# LDAQ-MOD-ADC8.net
KiCad netlist of a schematic drawn in EAGLE
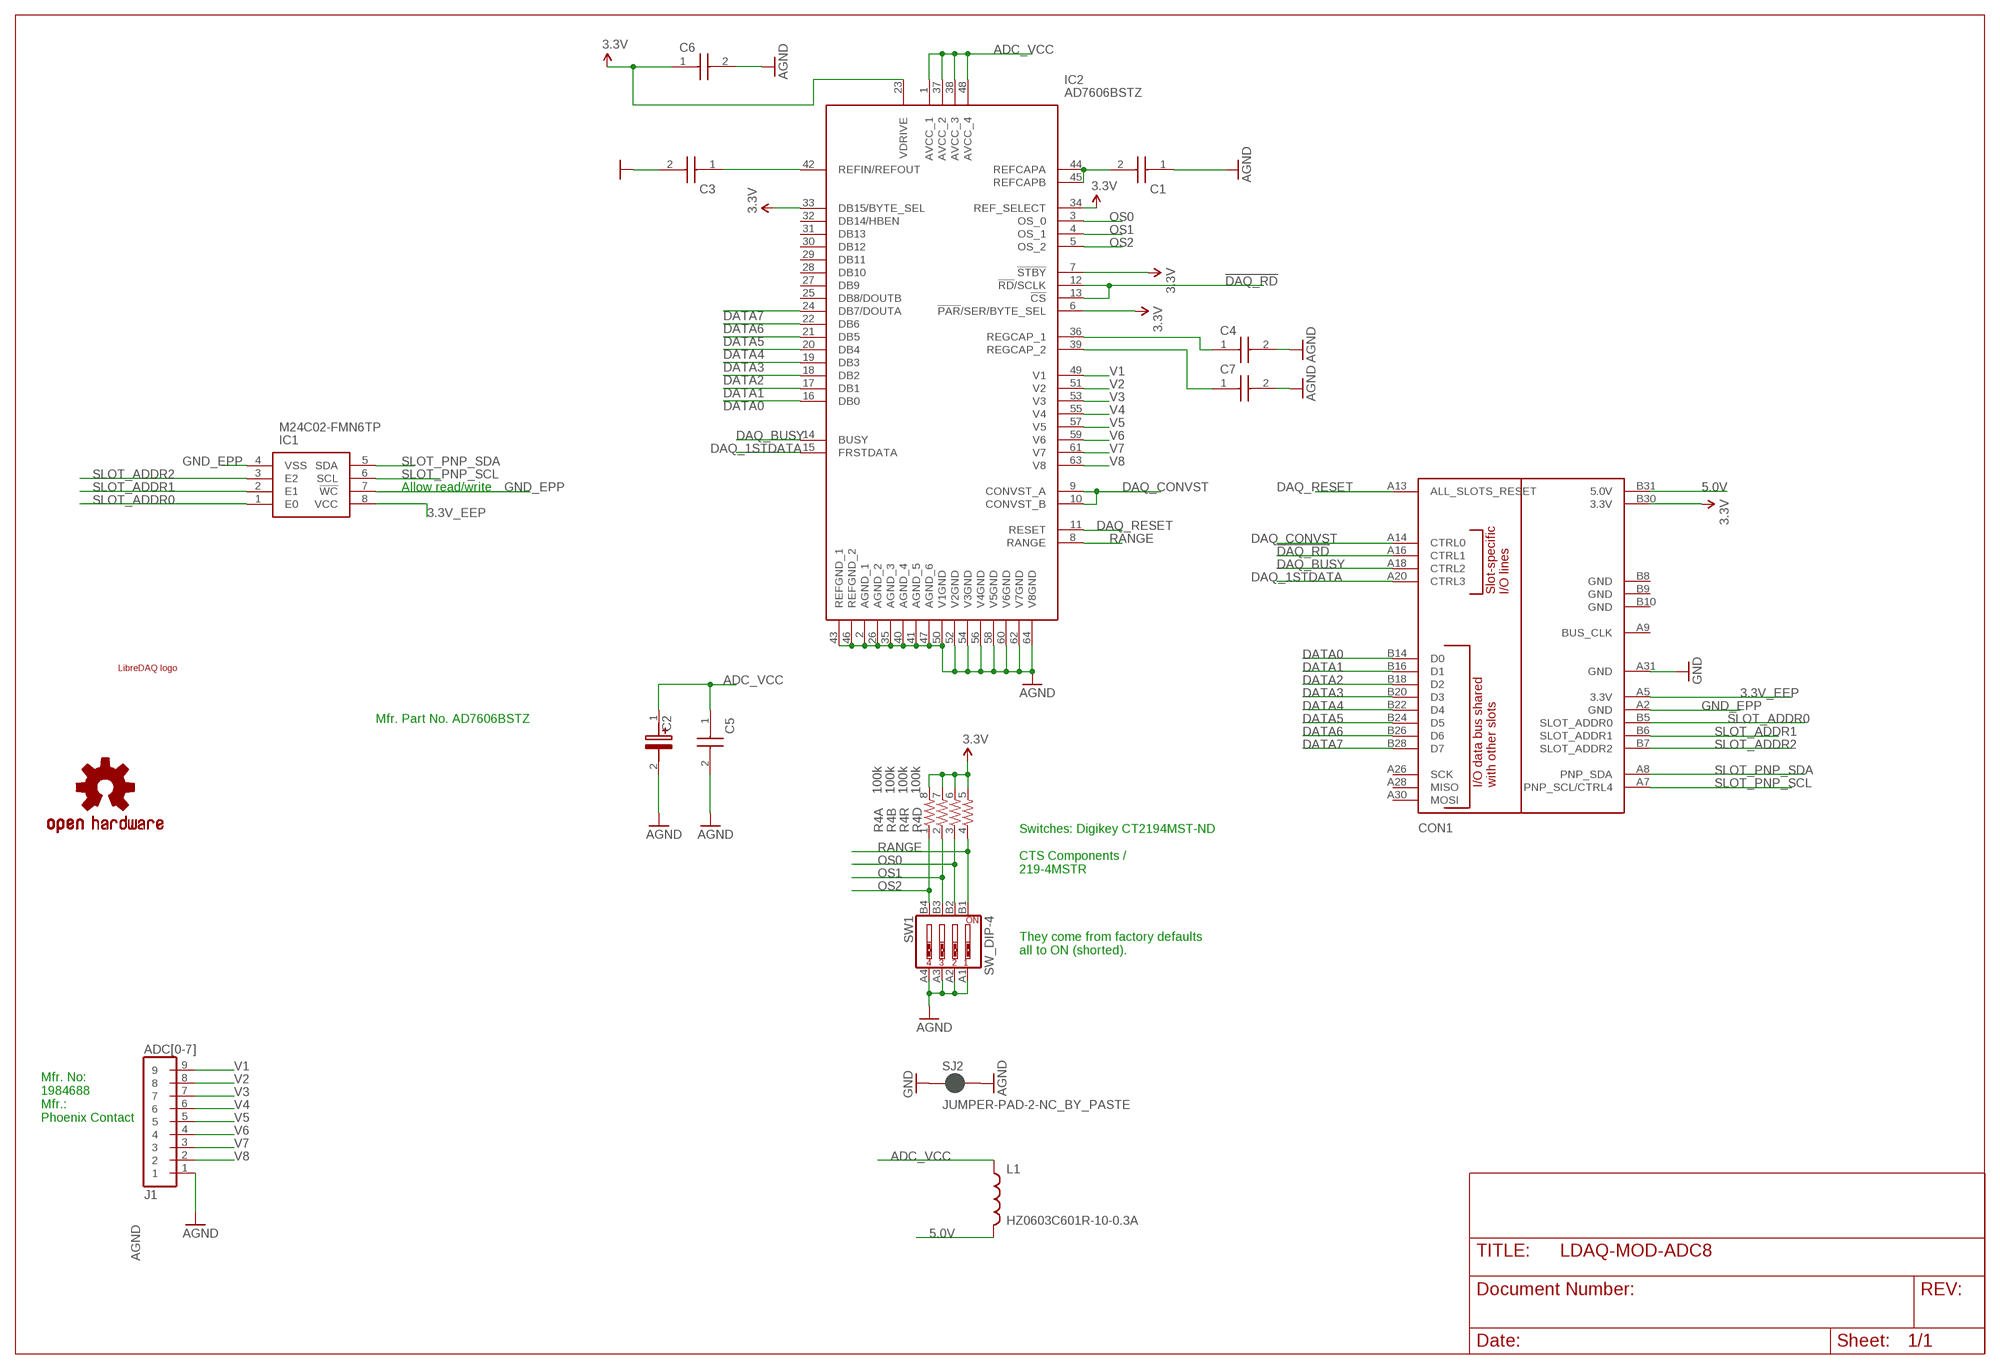
[diagram p0: schematic, sheet 1]

(export (version "E")
  (design (tool "Eeschema 10.0.6"))
  (components
    (comp (ref "C1")
      (value "10uF")
      (footprint "eagle-import:CAPC1005X55N")
      (fields
        (field (name "MANUFACTURER_PART_NUMBER") "LMK105BJ225KV-F")
        (field (name "MOUSER_PART_NUMBER") "963-LMK105BJ225KV-F")
      )
      (libsource (lib "eagle-import") (part "LMK105BJ225KV-F"))
    )
    (comp (ref "C2")
      (value "10uF")
      (footprint "eagle-import:CAPPM3528X210N")
      (fields
        (field (name "MANUFACTURER_PART_NUMBER") "TAJB226M010RNJ")
        (field (name "MOUSER_PART_NUMBER") "581-TAJB226M010R")
      )
      (libsource (lib "eagle-import") (part "TAJB226M010RNJ"))
    )
    (comp (ref "C3")
      (value "10uF")
      (footprint "eagle-import:CAPC1005X55N")
      (fields
        (field (name "MANUFACTURER_PART_NUMBER") "LMK105BJ225KV-F")
        (field (name "MOUSER_PART_NUMBER") "963-LMK105BJ225KV-F")
      )
      (libsource (lib "eagle-import") (part "LMK105BJ225KV-F"))
    )
    (comp (ref "C4")
      (value "1.0uF")
      (footprint "eagle-import:CAPC1005X55N")
      (fields
        (field (name "MANUFACTURER_PART_NUMBER") "LMK105BJ225KV-F")
        (field (name "MOUSER_PART_NUMBER") "963-LMK105BJ225KV-F")
      )
      (libsource (lib "eagle-import") (part "LMK105BJ225KV-F"))
    )
    (comp (ref "C5")
      (value "0.1uF")
      (footprint "eagle-import:CAPC1005X55N")
      (fields
        (field (name "MANUFACTURER_PART_NUMBER") "885012105010")
        (field (name "MOUSER_PART_NUMBER") "710-885012105010")
      )
      (libsource (lib "eagle-import") (part "885012105010"))
    )
    (comp (ref "C6")
      (value "0.1uF")
      (footprint "eagle-import:CAPC1005X55N")
      (fields
        (field (name "MANUFACTURER_PART_NUMBER") "885012105010")
        (field (name "MOUSER_PART_NUMBER") "710-885012105010")
      )
      (libsource (lib "eagle-import") (part "885012105010"))
    )
    (comp (ref "C7")
      (value "1.0uF")
      (footprint "eagle-import:CAPC1005X55N")
      (fields
        (field (name "MANUFACTURER_PART_NUMBER") "LMK105BJ225KV-F")
        (field (name "MOUSER_PART_NUMBER") "963-LMK105BJ225KV-F")
      )
      (libsource (lib "eagle-import") (part "LMK105BJ225KV-F"))
    )
    (comp (ref "CON1")
      (value "BOARD")
      (footprint "eagle-import:PCI-E_64_EDGE_63X50")
      (libsource (lib "eagle-import") (part "LIBREDAQ_DAUGHTER_BOARDPCIE-64-SIZE2"))
    )
    (comp (ref "IC1")
      (value "M24C02-FMN6TP")
      (footprint "eagle-import:SOIC127P600X175-8N")
      (fields (field (name "MOUSER_PART_NUMBER") "511-M24C02-FMN6TP"))
      (libsource (lib "eagle-import") (part "M24C02-FMN6TP"))
    )
    (comp (ref "IC2")
      (value "AD7606BSTZ")
      (footprint "eagle-import:QFP50P1200X1200X160-64N")
      (fields (field (name "MOUSER_PART_NUMBER") "584-AD7606BSTZ"))
      (libsource (lib "eagle-import") (part "AD7606BSTZ"))
    )
    (comp (ref "J1")
      (value "ADC[0-7]")
      (footprint "eagle-import:SCREWTERMINAL-3.5MM-9")
      (libsource (lib "eagle-import") (part "SCREWTERMINAL-3.5MM-9"))
    )
    (comp (ref "L1")
      (value "HZ0603C601R-10-0.3A")
      (footprint "eagle-import:0603")
      (libsource (lib "eagle-import") (part "INDUCTOR0603"))
    )
    (comp (ref "LOGO1")
      (value "LIBREDAQ_LOGO_MINILOGO_GENERIC")
      (footprint "eagle-import:LIBREDAQ_LOGO")
      (libsource (lib "eagle-import") (part "LIBREDAQ_LOGO_MINILOGO_GENERIC"))
    )
    (comp (ref "LOGO2")
      (value "OSHW-LOGOL")
      (footprint "eagle-import:OSHW-LOGO-L")
      (libsource (lib "eagle-import") (part "OSHW-LOGOL"))
    )
    (comp (ref "R4")
      (value "100k")
      (footprint "eagle-import:0603-ARV")
      (libsource (lib "eagle-import") (part "RESISTOR-ARRAY0603-ARV"))
    )
    (comp (ref "SJ2")
      (value "JUMPER-PAD-2-NC_BY_PASTE")
      (footprint "eagle-import:PAD-JUMPER-2-NC_BY_PASTE_YES_SILK")
      (libsource (lib "eagle-import") (part "JUMPER-PAD-2-NC_BY_PASTE"))
    )
    (comp (ref "SW1")
      (value "SW_DIP-4")
      (footprint "eagle-import:SW_SIP-4")
      (libsource (lib "eagle-import") (part "SW_DIP-4"))
    )
  )
  (nets
    (net (code "1") (name "/3.3V_EEP") (class "Default")
      (node (ref "CON1") (pin "A5") (pinfunction "3.3V_A5") (pintype "bidirectional"))
      (node (ref "IC1") (pin "8") (pinfunction "VCC_8") (pintype "bidirectional"))
    )
    (net (code "2") (name "/5.0V") (class "Default")
      (node (ref "CON1") (pin "B31") (pinfunction "5.0V_B31") (pintype "bidirectional"))
      (node (ref "L1") (pin "2") (pinfunction "2_2") (pintype "passive"))
    )
    (net (code "3") (name "/ADC_VCC") (class "Default")
      (node (ref "C2") (pin "1") (pinfunction "+_1") (pintype "bidirectional"))
      (node (ref "C5") (pin "1") (pinfunction "1_1") (pintype "bidirectional"))
      (node (ref "IC2") (pin "1") (pinfunction "AVCC_1_1") (pintype "bidirectional"))
      (node (ref "IC2") (pin "37") (pinfunction "AVCC_2_37") (pintype "bidirectional"))
      (node (ref "IC2") (pin "38") (pinfunction "AVCC_3_38") (pintype "bidirectional"))
      (node (ref "IC2") (pin "48") (pinfunction "AVCC_4_48") (pintype "bidirectional"))
      (node (ref "L1") (pin "1") (pinfunction "1_1") (pintype "passive"))
    )
    (net (code "4") (name "/DAQ_1STDATA") (class "Default")
      (node (ref "CON1") (pin "A20") (pinfunction "CTRL3_A20") (pintype "bidirectional"))
      (node (ref "IC2") (pin "15") (pinfunction "FRSTDATA_15") (pintype "bidirectional"))
    )
    (net (code "5") (name "/DAQ_BUSY") (class "Default")
      (node (ref "CON1") (pin "A18") (pinfunction "CTRL2_A18") (pintype "bidirectional"))
      (node (ref "IC2") (pin "14") (pinfunction "BUSY_14") (pintype "bidirectional"))
    )
    (net (code "6") (name "/DAQ_CONVST") (class "Default")
      (node (ref "CON1") (pin "A14") (pinfunction "CTRL0_A14") (pintype "bidirectional"))
      (node (ref "IC2") (pin "10") (pinfunction "CONVST_B_10") (pintype "bidirectional"))
      (node (ref "IC2") (pin "9") (pinfunction "CONVST_A_9") (pintype "bidirectional"))
    )
    (net (code "7") (name "/DAQ_RESET") (class "Default")
      (node (ref "CON1") (pin "A13") (pinfunction "ALL_SLOTS_RESET_A13") (pintype "bidirectional"))
      (node (ref "IC2") (pin "11") (pinfunction "RESET_11") (pintype "bidirectional"))
    )
    (net (code "8") (name "/DATA0") (class "Default")
      (node (ref "CON1") (pin "B14") (pinfunction "D0_B14") (pintype "bidirectional"))
      (node (ref "IC2") (pin "16") (pinfunction "DB0_16") (pintype "bidirectional"))
    )
    (net (code "9") (name "/DATA1") (class "Default")
      (node (ref "CON1") (pin "B16") (pinfunction "D1_B16") (pintype "bidirectional"))
      (node (ref "IC2") (pin "17") (pinfunction "DB1_17") (pintype "bidirectional"))
    )
    (net (code "10") (name "/DATA2") (class "Default")
      (node (ref "CON1") (pin "B18") (pinfunction "D2_B18") (pintype "bidirectional"))
      (node (ref "IC2") (pin "18") (pinfunction "DB2_18") (pintype "bidirectional"))
    )
    (net (code "11") (name "/DATA3") (class "Default")
      (node (ref "CON1") (pin "B20") (pinfunction "D3_B20") (pintype "bidirectional"))
      (node (ref "IC2") (pin "19") (pinfunction "DB3_19") (pintype "bidirectional"))
    )
    (net (code "12") (name "/DATA4") (class "Default")
      (node (ref "CON1") (pin "B22") (pinfunction "D4_B22") (pintype "bidirectional"))
      (node (ref "IC2") (pin "20") (pinfunction "DB4_20") (pintype "bidirectional"))
    )
    (net (code "13") (name "/DATA5") (class "Default")
      (node (ref "CON1") (pin "B24") (pinfunction "D5_B24") (pintype "bidirectional"))
      (node (ref "IC2") (pin "21") (pinfunction "DB5_21") (pintype "bidirectional"))
    )
    (net (code "14") (name "/DATA6") (class "Default")
      (node (ref "CON1") (pin "B26") (pinfunction "D6_B26") (pintype "bidirectional"))
      (node (ref "IC2") (pin "22") (pinfunction "DB6_22") (pintype "bidirectional"))
    )
    (net (code "15") (name "/DATA7") (class "Default")
      (node (ref "CON1") (pin "B28") (pinfunction "D7_B28") (pintype "bidirectional"))
      (node (ref "IC2") (pin "24") (pinfunction "DB7/DOUTA_24") (pintype "bidirectional"))
    )
    (net (code "16") (name "/GND_EPP") (class "Default")
      (node (ref "CON1") (pin "A2") (pinfunction "GND_A2") (pintype "bidirectional"))
      (node (ref "IC1") (pin "4") (pinfunction "VSS_4") (pintype "bidirectional"))
      (node (ref "IC1") (pin "7") (pinfunction "~{WC}_7") (pintype "bidirectional"))
    )
    (net (code "17") (name "/OS0") (class "Default")
      (node (ref "IC2") (pin "3") (pinfunction "OS_0_3") (pintype "bidirectional"))
      (node (ref "R4") (pin "3") (pinfunction "1_3") (pintype "passive"))
      (node (ref "SW1") (pin "B2") (pinfunction "B2_B2") (pintype "passive"))
    )
    (net (code "18") (name "/OS1") (class "Default")
      (node (ref "IC2") (pin "4") (pinfunction "OS_1_4") (pintype "bidirectional"))
      (node (ref "R4") (pin "2") (pinfunction "1_2") (pintype "passive"))
      (node (ref "SW1") (pin "B3") (pinfunction "B3_B3") (pintype "passive"))
    )
    (net (code "19") (name "/OS2") (class "Default")
      (node (ref "IC2") (pin "5") (pinfunction "OS_2_5") (pintype "bidirectional"))
      (node (ref "R4") (pin "1") (pinfunction "1_1") (pintype "passive"))
      (node (ref "SW1") (pin "B4") (pinfunction "B4_B4") (pintype "passive"))
    )
    (net (code "20") (name "/RANGE") (class "Default")
      (node (ref "IC2") (pin "8") (pinfunction "RANGE_8") (pintype "bidirectional"))
      (node (ref "R4") (pin "4") (pinfunction "1_4") (pintype "passive"))
      (node (ref "SW1") (pin "B1") (pinfunction "B1_B1") (pintype "passive"))
    )
    (net (code "21") (name "/SLOT_ADDR0") (class "Default")
      (node (ref "CON1") (pin "B5") (pinfunction "SLOT_ADDR0_B5") (pintype "bidirectional"))
      (node (ref "IC1") (pin "1") (pinfunction "E0_1") (pintype "bidirectional"))
    )
    (net (code "22") (name "/SLOT_ADDR1") (class "Default")
      (node (ref "CON1") (pin "B6") (pinfunction "SLOT_ADDR1_B6") (pintype "bidirectional"))
      (node (ref "IC1") (pin "2") (pinfunction "E1_2") (pintype "bidirectional"))
    )
    (net (code "23") (name "/SLOT_ADDR2") (class "Default")
      (node (ref "CON1") (pin "B7") (pinfunction "SLOT_ADDR2_B7") (pintype "bidirectional"))
      (node (ref "IC1") (pin "3") (pinfunction "E2_3") (pintype "bidirectional"))
    )
    (net (code "24") (name "/SLOT_PNP_SCL") (class "Default")
      (node (ref "CON1") (pin "A7") (pinfunction "PNP_SCL/CTRL4_A7") (pintype "bidirectional"))
      (node (ref "IC1") (pin "6") (pinfunction "SCL_6") (pintype "bidirectional"))
    )
    (net (code "25") (name "/SLOT_PNP_SDA") (class "Default")
      (node (ref "CON1") (pin "A8") (pinfunction "PNP_SDA_A8") (pintype "bidirectional"))
      (node (ref "IC1") (pin "5") (pinfunction "SDA_5") (pintype "bidirectional"))
    )
    (net (code "26") (name "/V1") (class "Default")
      (node (ref "IC2") (pin "49") (pinfunction "V1_49") (pintype "bidirectional"))
      (node (ref "J1") (pin "9") (pinfunction "9_9") (pintype "bidirectional"))
    )
    (net (code "27") (name "/V2") (class "Default")
      (node (ref "IC2") (pin "51") (pinfunction "V2_51") (pintype "bidirectional"))
      (node (ref "J1") (pin "8") (pinfunction "8_8") (pintype "bidirectional"))
    )
    (net (code "28") (name "/V3") (class "Default")
      (node (ref "IC2") (pin "53") (pinfunction "V3_53") (pintype "bidirectional"))
      (node (ref "J1") (pin "7") (pinfunction "7_7") (pintype "bidirectional"))
    )
    (net (code "29") (name "/V4") (class "Default")
      (node (ref "IC2") (pin "55") (pinfunction "V4_55") (pintype "bidirectional"))
      (node (ref "J1") (pin "6") (pinfunction "6_6") (pintype "bidirectional"))
    )
    (net (code "30") (name "/V5") (class "Default")
      (node (ref "IC2") (pin "57") (pinfunction "V5_57") (pintype "bidirectional"))
      (node (ref "J1") (pin "5") (pinfunction "5_5") (pintype "bidirectional"))
    )
    (net (code "31") (name "/V6") (class "Default")
      (node (ref "IC2") (pin "59") (pinfunction "V6_59") (pintype "bidirectional"))
      (node (ref "J1") (pin "4") (pinfunction "4_4") (pintype "bidirectional"))
    )
    (net (code "32") (name "/V7") (class "Default")
      (node (ref "IC2") (pin "61") (pinfunction "V7_61") (pintype "bidirectional"))
      (node (ref "J1") (pin "3") (pinfunction "3_3") (pintype "bidirectional"))
    )
    (net (code "33") (name "/V8") (class "Default")
      (node (ref "IC2") (pin "63") (pinfunction "V8_63") (pintype "bidirectional"))
      (node (ref "J1") (pin "2") (pinfunction "2_2") (pintype "bidirectional"))
    )
    (net (code "34") (name "/~{DAQ_RD}") (class "Default")
      (node (ref "CON1") (pin "A16") (pinfunction "CTRL1_A16") (pintype "bidirectional"))
      (node (ref "IC2") (pin "12") (pinfunction "~{RD}/SCLK_12") (pintype "bidirectional"))
      (node (ref "IC2") (pin "13") (pinfunction "~{CS}_13") (pintype "bidirectional"))
    )
    (net (code "35") (name "3.3V") (class "Default")
      (node (ref "C6") (pin "1") (pinfunction "1_1") (pintype "bidirectional"))
      (node (ref "CON1") (pin "B30") (pinfunction "3.3V_B30") (pintype "bidirectional"))
      (node (ref "IC2") (pin "23") (pinfunction "VDRIVE_23") (pintype "bidirectional"))
      (node (ref "IC2") (pin "33") (pinfunction "DB15/BYTE_SEL_33") (pintype "bidirectional"))
      (node (ref "IC2") (pin "34") (pinfunction "REF_SELECT_34") (pintype "bidirectional"))
      (node (ref "IC2") (pin "6") (pinfunction "~{PAR}/SER/BYTE_SEL_6") (pintype "bidirectional"))
      (node (ref "IC2") (pin "7") (pinfunction "~{STBY}_7") (pintype "bidirectional"))
      (node (ref "R4") (pin "5") (pinfunction "2_5") (pintype "passive"))
      (node (ref "R4") (pin "6") (pinfunction "2_6") (pintype "passive"))
      (node (ref "R4") (pin "7") (pinfunction "2_7") (pintype "passive"))
      (node (ref "R4") (pin "8") (pinfunction "2_8") (pintype "passive"))
    )
    (net (code "36") (name "AGND") (class "Default")
      (node (ref "C1") (pin "1") (pinfunction "1_1") (pintype "bidirectional"))
      (node (ref "C2") (pin "2") (pinfunction "-_2") (pintype "bidirectional"))
      (node (ref "C3") (pin "2") (pinfunction "2_2") (pintype "bidirectional"))
      (node (ref "C4") (pin "2") (pinfunction "2_2") (pintype "bidirectional"))
      (node (ref "C5") (pin "2") (pinfunction "2_2") (pintype "bidirectional"))
      (node (ref "C6") (pin "2") (pinfunction "2_2") (pintype "bidirectional"))
      (node (ref "C7") (pin "2") (pinfunction "2_2") (pintype "bidirectional"))
      (node (ref "IC2") (pin "2") (pinfunction "AGND_1_2") (pintype "bidirectional"))
      (node (ref "IC2") (pin "26") (pinfunction "AGND_2_26") (pintype "bidirectional"))
      (node (ref "IC2") (pin "35") (pinfunction "AGND_3_35") (pintype "bidirectional"))
      (node (ref "IC2") (pin "40") (pinfunction "AGND_4_40") (pintype "bidirectional"))
      (node (ref "IC2") (pin "41") (pinfunction "AGND_5_41") (pintype "bidirectional"))
      (node (ref "IC2") (pin "43") (pinfunction "REFGND_1_43") (pintype "bidirectional"))
      (node (ref "IC2") (pin "46") (pinfunction "REFGND_2_46") (pintype "bidirectional"))
      (node (ref "IC2") (pin "47") (pinfunction "AGND_6_47") (pintype "bidirectional"))
      (node (ref "IC2") (pin "50") (pinfunction "V1GND_50") (pintype "bidirectional"))
      (node (ref "IC2") (pin "52") (pinfunction "V2GND_52") (pintype "bidirectional"))
      (node (ref "IC2") (pin "54") (pinfunction "V3GND_54") (pintype "bidirectional"))
      (node (ref "IC2") (pin "56") (pinfunction "V4GND_56") (pintype "bidirectional"))
      (node (ref "IC2") (pin "58") (pinfunction "V5GND_58") (pintype "bidirectional"))
      (node (ref "IC2") (pin "60") (pinfunction "V6GND_60") (pintype "bidirectional"))
      (node (ref "IC2") (pin "62") (pinfunction "V7GND_62") (pintype "bidirectional"))
      (node (ref "IC2") (pin "64") (pinfunction "V8GND_64") (pintype "bidirectional"))
      (node (ref "J1") (pin "1") (pinfunction "1_1") (pintype "bidirectional"))
      (node (ref "SJ2") (pin "2") (pinfunction "2_2") (pintype "passive"))
      (node (ref "SW1") (pin "A1") (pinfunction "A1_A1") (pintype "passive"))
      (node (ref "SW1") (pin "A2") (pinfunction "A2_A2") (pintype "passive"))
      (node (ref "SW1") (pin "A3") (pinfunction "A3_A3") (pintype "passive"))
      (node (ref "SW1") (pin "A4") (pinfunction "A4_A4") (pintype "passive"))
    )
    (net (code "37") (name "GND") (class "Default")
      (node (ref "CON1") (pin "A31") (pinfunction "GND_A31") (pintype "bidirectional"))
      (node (ref "SJ2") (pin "1") (pinfunction "1_1") (pintype "passive"))
    )
    (net (code "38") (name "Net-(IC2-REFCAPA)") (class "Default")
      (node (ref "C1") (pin "2") (pinfunction "2_2") (pintype "bidirectional"))
      (node (ref "IC2") (pin "44") (pinfunction "REFCAPA_44") (pintype "bidirectional"))
      (node (ref "IC2") (pin "45") (pinfunction "REFCAPB_45") (pintype "bidirectional"))
    )
    (net (code "39") (name "Net-(IC2-REFIN{slash}REFOUT)") (class "Default")
      (node (ref "C3") (pin "1") (pinfunction "1_1") (pintype "bidirectional"))
      (node (ref "IC2") (pin "42") (pinfunction "REFIN/REFOUT_42") (pintype "bidirectional"))
    )
    (net (code "40") (name "Net-(IC2-REGCAP_1)") (class "Default")
      (node (ref "C4") (pin "1") (pinfunction "1_1") (pintype "bidirectional"))
      (node (ref "IC2") (pin "36") (pinfunction "REGCAP_1_36") (pintype "bidirectional"))
    )
    (net (code "41") (name "Net-(IC2-REGCAP_2)") (class "Default")
      (node (ref "C7") (pin "1") (pinfunction "1_1") (pintype "bidirectional"))
      (node (ref "IC2") (pin "39") (pinfunction "REGCAP_2_39") (pintype "bidirectional"))
    )
    (net (code "42") (name "unconnected-(CON1-BUS_CLK-PadA9)") (class "Default")
      (node (ref "CON1") (pin "A9") (pinfunction "BUS_CLK_A9") (pintype "bidirectional"))
    )
    (net (code "43") (name "unconnected-(CON1-GND-PadB8)") (class "Default")
      (node (ref "CON1") (pin "B8") (pinfunction "GND_B8") (pintype "bidirectional"))
    )
    (net (code "44") (name "unconnected-(CON1-GND-PadB9)") (class "Default")
      (node (ref "CON1") (pin "B9") (pinfunction "GND_B9") (pintype "bidirectional"))
    )
    (net (code "45") (name "unconnected-(CON1-GND-PadB10)") (class "Default")
      (node (ref "CON1") (pin "B10") (pinfunction "GND_B10") (pintype "bidirectional"))
    )
    (net (code "46") (name "unconnected-(CON1-MISO-PadA28)") (class "Default")
      (node (ref "CON1") (pin "A28") (pinfunction "MISO_A28") (pintype "bidirectional"))
    )
    (net (code "47") (name "unconnected-(CON1-MOSI-PadA30)") (class "Default")
      (node (ref "CON1") (pin "A30") (pinfunction "MOSI_A30") (pintype "bidirectional"))
    )
    (net (code "48") (name "unconnected-(CON1-SCK-PadA26)") (class "Default")
      (node (ref "CON1") (pin "A26") (pinfunction "SCK_A26") (pintype "bidirectional"))
    )
    (net (code "49") (name "unconnected-(IC2-DB8{slash}DOUTB-Pad25)") (class "Default")
      (node (ref "IC2") (pin "25") (pinfunction "DB8/DOUTB_25") (pintype "bidirectional"))
    )
    (net (code "50") (name "unconnected-(IC2-DB9-Pad27)") (class "Default")
      (node (ref "IC2") (pin "27") (pinfunction "DB9_27") (pintype "bidirectional"))
    )
    (net (code "51") (name "unconnected-(IC2-DB10-Pad28)") (class "Default")
      (node (ref "IC2") (pin "28") (pinfunction "DB10_28") (pintype "bidirectional"))
    )
    (net (code "52") (name "unconnected-(IC2-DB11-Pad29)") (class "Default")
      (node (ref "IC2") (pin "29") (pinfunction "DB11_29") (pintype "bidirectional"))
    )
    (net (code "53") (name "unconnected-(IC2-DB12-Pad30)") (class "Default")
      (node (ref "IC2") (pin "30") (pinfunction "DB12_30") (pintype "bidirectional"))
    )
    (net (code "54") (name "unconnected-(IC2-DB13-Pad31)") (class "Default")
      (node (ref "IC2") (pin "31") (pinfunction "DB13_31") (pintype "bidirectional"))
    )
    (net (code "55") (name "unconnected-(IC2-DB14{slash}HBEN-Pad32)") (class "Default")
      (node (ref "IC2") (pin "32") (pinfunction "DB14/HBEN_32") (pintype "bidirectional"))
    )
  )
)
